# 05_slave-connector.net
KiCad netlist of a schematic drawn in Altium Designer
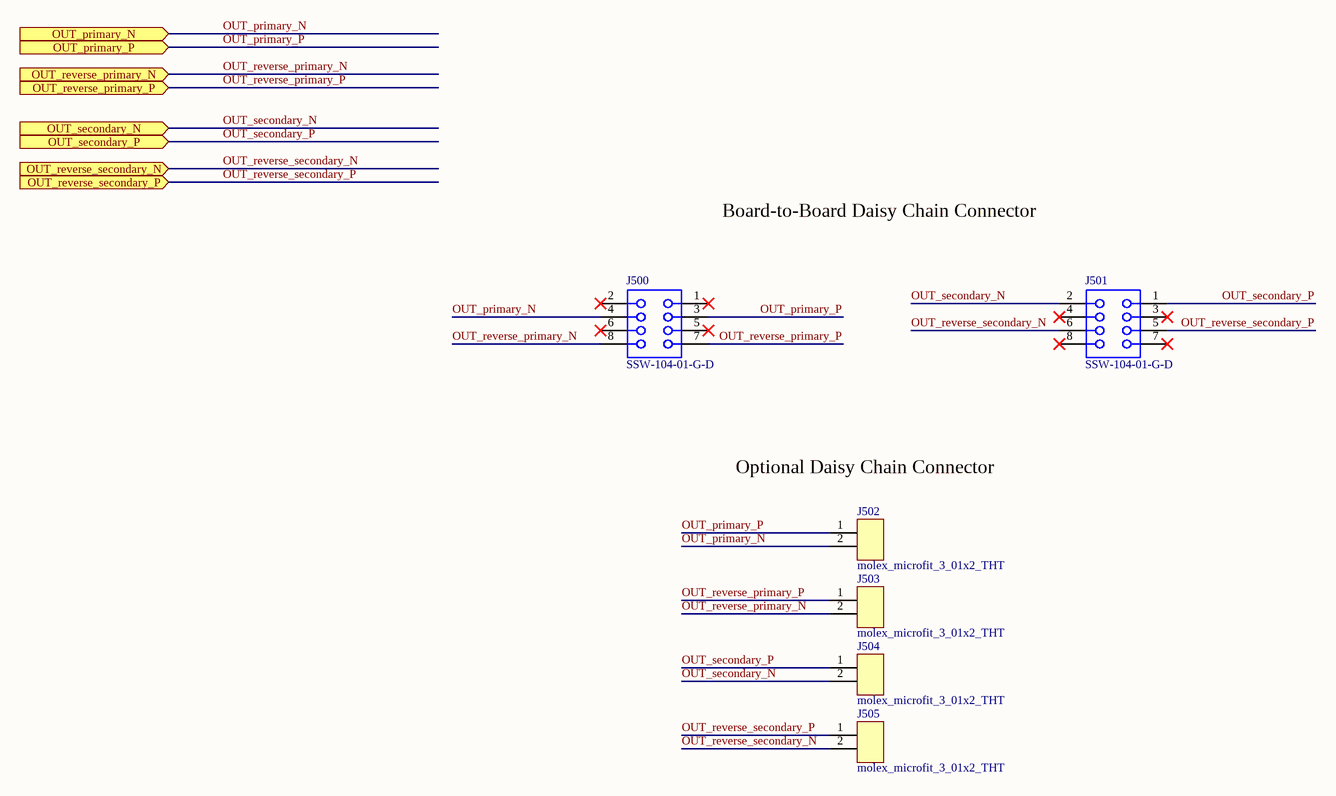
[diagram p0: 05_slave-connector.SchDoc]

(export (version "E")
  (design (tool "Eeschema 10.0.6"))
  (components
    (comp (ref "J500")
      (value "SSW-104-01-G-D")
      (footprint "SMTC-SSW-104-01-X-D")
      (description "SQ Post Socket, Through-hole, Vertical, -55 to 125 degC, 2.54mm Pitch, 8-Pin, Female, RoHS")
      (fields (field (name "MANUFACTURER") "Samtec"))
      (libsource (lib "Altium Content Vault") (part "SMTC-SSW-104-X-X-D"))
    )
    (comp (ref "J501")
      (value "SSW-104-01-G-D")
      (footprint "SMTC-SSW-104-01-X-D")
      (description "SQ Post Socket, Through-hole, Vertical, -55 to 125 degC, 2.54mm Pitch, 8-Pin, Female, RoHS")
      (fields (field (name "MANUFACTURER") "Samtec"))
      (libsource (lib "Altium Content Vault") (part "SMTC-SSW-104-X-X-D"))
    )
    (comp (ref "J502")
      (value "molex_microfit_3_01x2_THT")
      (footprint "MOLEX_MICROFIT_01x2_THT")
      (fields (field (name "MANUFACTURER") "Molex"))
      (libsource (lib "OE750") (part "X2"))
    )
    (comp (ref "J503")
      (value "molex_microfit_3_01x2_THT")
      (footprint "MOLEX_MICROFIT_01x2_THT")
      (fields (field (name "MANUFACTURER") "Molex"))
      (libsource (lib "OE750") (part "X2"))
    )
    (comp (ref "J504")
      (value "molex_microfit_3_01x2_THT")
      (footprint "MOLEX_MICROFIT_01x2_THT")
      (fields (field (name "MANUFACTURER") "Molex"))
      (libsource (lib "OE750") (part "X2"))
    )
    (comp (ref "J505")
      (value "molex_microfit_3_01x2_THT")
      (footprint "MOLEX_MICROFIT_01x2_THT")
      (fields (field (name "MANUFACTURER") "Molex"))
      (libsource (lib "OE750") (part "X2"))
    )
  )
  (nets
    (net (code "1") (name "/OUT_primary_N") (class "Default")
      (node (ref "J500") (pin "4") (pinfunction "4_4") (pintype "passive"))
      (node (ref "J502") (pin "2") (pintype "passive"))
    )
    (net (code "2") (name "/OUT_primary_P") (class "Default")
      (node (ref "J500") (pin "3") (pinfunction "3_3") (pintype "passive"))
      (node (ref "J502") (pin "1") (pintype "passive"))
    )
    (net (code "3") (name "/OUT_reverse_primary_N") (class "Default")
      (node (ref "J500") (pin "8") (pinfunction "8_8") (pintype "passive"))
      (node (ref "J503") (pin "2") (pintype "passive"))
    )
    (net (code "4") (name "/OUT_reverse_primary_P") (class "Default")
      (node (ref "J500") (pin "7") (pinfunction "7_7") (pintype "passive"))
      (node (ref "J503") (pin "1") (pintype "passive"))
    )
    (net (code "5") (name "/OUT_reverse_secondary_N") (class "Default")
      (node (ref "J501") (pin "6") (pinfunction "6_6") (pintype "passive"))
      (node (ref "J505") (pin "2") (pintype "passive"))
    )
    (net (code "6") (name "/OUT_reverse_secondary_P") (class "Default")
      (node (ref "J501") (pin "5") (pinfunction "5_5") (pintype "passive"))
      (node (ref "J505") (pin "1") (pintype "passive"))
    )
    (net (code "7") (name "/OUT_secondary_N") (class "Default")
      (node (ref "J501") (pin "2") (pinfunction "2_2") (pintype "passive"))
      (node (ref "J504") (pin "2") (pintype "passive"))
    )
    (net (code "8") (name "/OUT_secondary_P") (class "Default")
      (node (ref "J501") (pin "1") (pinfunction "1_1") (pintype "passive"))
      (node (ref "J504") (pin "1") (pintype "passive"))
    )
    (net (code "9") (name "unconnected-(J500-Pad1)") (class "Default")
      (node (ref "J500") (pin "1") (pinfunction "1_1") (pintype "passive+no_connect"))
    )
    (net (code "10") (name "unconnected-(J500-Pad2)") (class "Default")
      (node (ref "J500") (pin "2") (pinfunction "2_2") (pintype "passive+no_connect"))
    )
    (net (code "11") (name "unconnected-(J500-Pad5)") (class "Default")
      (node (ref "J500") (pin "5") (pinfunction "5_5") (pintype "passive+no_connect"))
    )
    (net (code "12") (name "unconnected-(J500-Pad6)") (class "Default")
      (node (ref "J500") (pin "6") (pinfunction "6_6") (pintype "passive+no_connect"))
    )
    (net (code "13") (name "unconnected-(J501-Pad3)") (class "Default")
      (node (ref "J501") (pin "3") (pinfunction "3_3") (pintype "passive+no_connect"))
    )
    (net (code "14") (name "unconnected-(J501-Pad4)") (class "Default")
      (node (ref "J501") (pin "4") (pinfunction "4_4") (pintype "passive+no_connect"))
    )
    (net (code "15") (name "unconnected-(J501-Pad7)") (class "Default")
      (node (ref "J501") (pin "7") (pinfunction "7_7") (pintype "passive+no_connect"))
    )
    (net (code "16") (name "unconnected-(J501-Pad8)") (class "Default")
      (node (ref "J501") (pin "8") (pinfunction "8_8") (pintype "passive+no_connect"))
    )
  )
)
